# microvboatBOARD.net
KiCad netlist of a schematic drawn in EAGLE
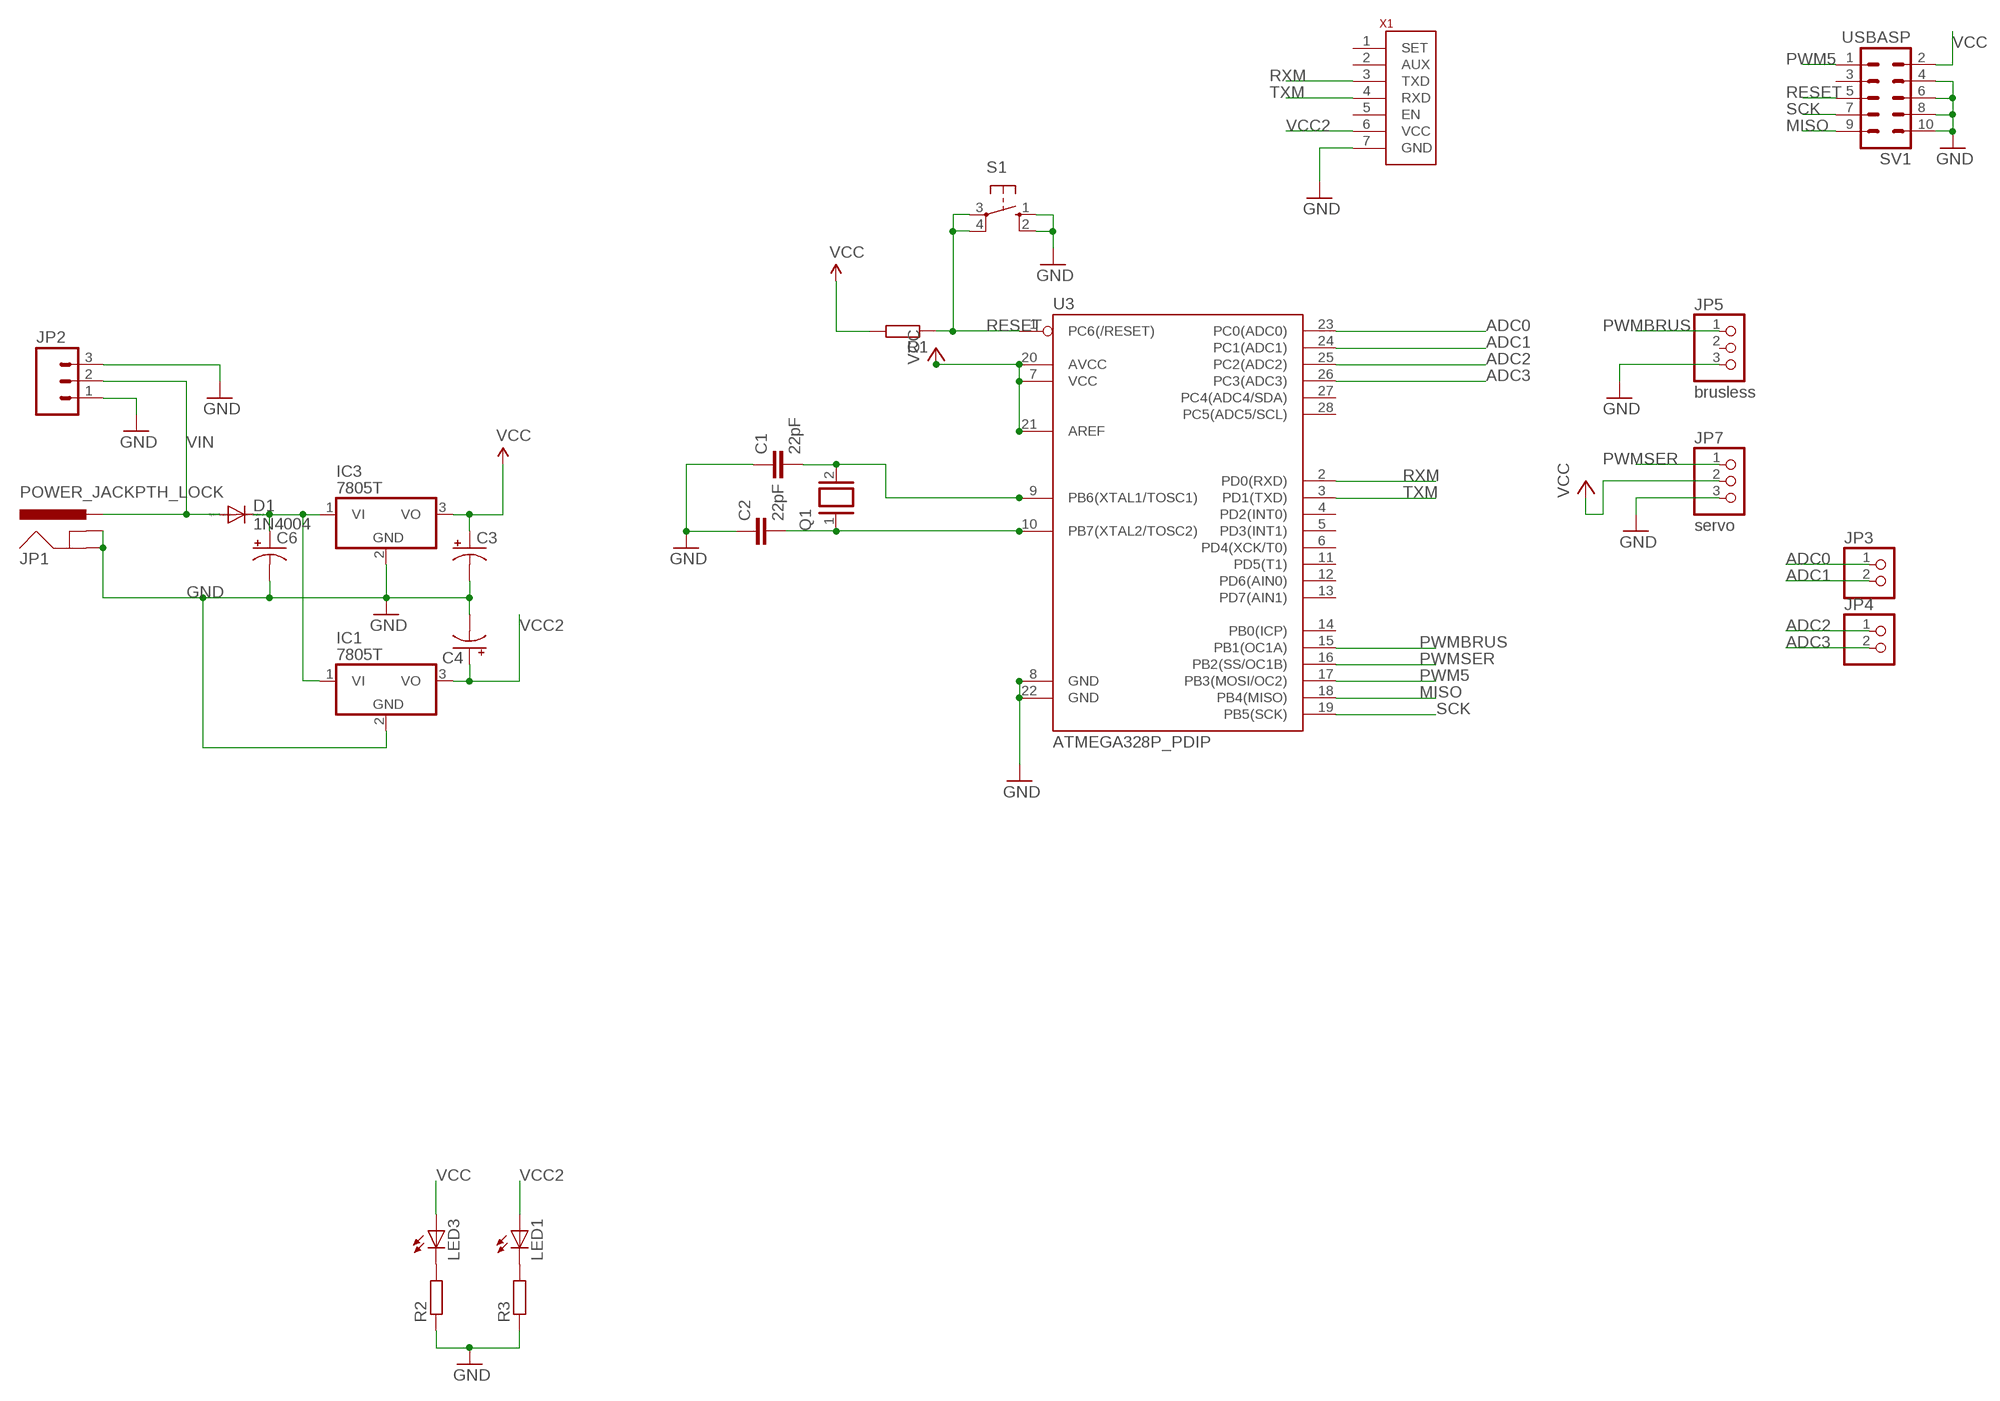
[diagram p0: schematic, sheet 1]

(export (version "E")
  (design (tool "Eeschema 10.0.6"))
  (components
    (comp (ref "C1")
      (value "22pF")
      (footprint "eagle-import:C2.5-3")
      (libsource (lib "eagle-import") (part "C2,5-3"))
    )
    (comp (ref "C2")
      (value "22pF")
      (footprint "eagle-import:C2.5-3")
      (libsource (lib "eagle-import") (part "C2,5-3"))
    )
    (comp (ref "C3")
      (value "CPOL-USE2.5-5")
      (footprint "eagle-import:E2,5-5")
      (libsource (lib "eagle-import") (part "CPOL-USE2.5-5"))
    )
    (comp (ref "C4")
      (value "CPOL-USE2.5-5")
      (footprint "eagle-import:E2,5-5")
      (libsource (lib "eagle-import") (part "CPOL-USE2.5-5"))
    )
    (comp (ref "C6")
      (value "CPOL-USE2.5-5")
      (footprint "eagle-import:E2,5-5")
      (libsource (lib "eagle-import") (part "CPOL-USE2.5-5"))
    )
    (comp (ref "D1")
      (value "1N4004")
      (footprint "eagle-import:DO41-10")
      (libsource (lib "eagle-import") (part "1N4004"))
    )
    (comp (ref "IC1")
      (value "7805T")
      (footprint "eagle-import:TO220H")
      (libsource (lib "eagle-import") (part "78T05"))
    )
    (comp (ref "IC3")
      (value "7805T")
      (footprint "eagle-import:TO220H")
      (libsource (lib "eagle-import") (part "78T05"))
    )
    (comp (ref "JP1")
      (value "POWER_JACKPTH_LOCK")
      (footprint "eagle-import:POWER_JACK_PTH_LOCK")
      (libsource (lib "eagle-import") (part "POWER_JACKPTH_LOCK"))
    )
    (comp (ref "JP2")
      (value "M03POLAR")
      (footprint "eagle-import:MOLEX-1X3")
      (libsource (lib "eagle-import") (part "M03POLAR"))
    )
    (comp (ref "JP3")
      (value "PINHD-1X2")
      (footprint "eagle-import:1X02")
      (libsource (lib "eagle-import") (part "PINHD-1X2"))
    )
    (comp (ref "JP4")
      (value "PINHD-1X2")
      (footprint "eagle-import:1X02")
      (libsource (lib "eagle-import") (part "PINHD-1X2"))
    )
    (comp (ref "JP5")
      (value "brusless")
      (footprint "eagle-import:1X03")
      (libsource (lib "eagle-import") (part "PINHD-1X3"))
    )
    (comp (ref "JP7")
      (value "servo")
      (footprint "eagle-import:1X03")
      (libsource (lib "eagle-import") (part "PINHD-1X3"))
    )
    (comp (ref "LED1")
      (value "LED3MM")
      (footprint "eagle-import:LED3MM")
      (libsource (lib "eagle-import") (part "LED3MM"))
    )
    (comp (ref "LED3")
      (value "LED3MM")
      (footprint "eagle-import:LED3MM")
      (libsource (lib "eagle-import") (part "LED3MM"))
    )
    (comp (ref "Q1")
      (value "XTAL/S")
      (footprint "eagle-import:QS")
      (libsource (lib "eagle-import") (part "XTAL/S"))
    )
    (comp (ref "R1")
      (value "R-EU_0204/7")
      (footprint "eagle-import:0204_7")
      (libsource (lib "eagle-import") (part "R-EU_0204/7"))
    )
    (comp (ref "R2")
      (value "R-EU_0204/7")
      (footprint "eagle-import:0204_7")
      (libsource (lib "eagle-import") (part "R-EU_0204/7"))
    )
    (comp (ref "R3")
      (value "R-EU_0204/7")
      (footprint "eagle-import:0204_7")
      (libsource (lib "eagle-import") (part "R-EU_0204/7"))
    )
    (comp (ref "S1")
      (value "10-XX")
      (footprint "eagle-import:B3F-10XX")
      (fields (field (name "MPN") "B3F-1000"))
      (libsource (lib "eagle-import") (part "10-XX"))
    )
    (comp (ref "SV1")
      (value "USBASP")
      (footprint "eagle-import:ML10")
      (libsource (lib "eagle-import") (part "ML10"))
    )
    (comp (ref "U3")
      (value "ATMEGA328P_PDIP")
      (footprint "eagle-import:DIL28-3")
      (libsource (lib "eagle-import") (part "ATMEGA328P_PDIP"))
    )
    (comp (ref "X1")
      (value "APC220")
      (footprint "eagle-import:APC220")
      (libsource (lib "eagle-import") (part "APC220"))
    )
  )
  (nets
    (net (code "1") (name "/ADC0") (class "Default")
      (node (ref "JP3") (pin "1") (pinfunction "1_1") (pintype "passive"))
      (node (ref "U3") (pin "23") (pinfunction "PC0(ADC0)_23") (pintype "bidirectional"))
    )
    (net (code "2") (name "/ADC1") (class "Default")
      (node (ref "JP3") (pin "2") (pinfunction "2_2") (pintype "passive"))
      (node (ref "U3") (pin "24") (pinfunction "PC1(ADC1)_24") (pintype "bidirectional"))
    )
    (net (code "3") (name "/ADC2") (class "Default")
      (node (ref "JP4") (pin "1") (pinfunction "1_1") (pintype "passive"))
      (node (ref "U3") (pin "25") (pinfunction "PC2(ADC2)_25") (pintype "bidirectional"))
    )
    (net (code "4") (name "/ADC3") (class "Default")
      (node (ref "JP4") (pin "2") (pinfunction "2_2") (pintype "passive"))
      (node (ref "U3") (pin "26") (pinfunction "PC3(ADC3)_26") (pintype "bidirectional"))
    )
    (net (code "5") (name "/MISO") (class "Default")
      (node (ref "SV1") (pin "9") (pinfunction "9_9") (pintype "passive"))
      (node (ref "U3") (pin "18") (pinfunction "PB4(MISO)_18") (pintype "bidirectional"))
    )
    (net (code "6") (name "/PWM5") (class "Default")
      (node (ref "SV1") (pin "1") (pinfunction "1_1") (pintype "passive"))
      (node (ref "U3") (pin "17") (pinfunction "PB3(MOSI/OC2)_17") (pintype "bidirectional"))
    )
    (net (code "7") (name "/PWMBRUS") (class "Default")
      (node (ref "JP5") (pin "1") (pinfunction "1_1") (pintype "passive"))
      (node (ref "U3") (pin "15") (pinfunction "PB1(OC1A)_15") (pintype "bidirectional"))
    )
    (net (code "8") (name "/PWMSER") (class "Default")
      (node (ref "JP7") (pin "1") (pinfunction "1_1") (pintype "passive"))
      (node (ref "U3") (pin "16") (pinfunction "PB2(SS/OC1B)_16") (pintype "bidirectional"))
    )
    (net (code "9") (name "/RESET") (class "Default")
      (node (ref "R1") (pin "1") (pinfunction "1_1") (pintype "passive"))
      (node (ref "S1") (pin "3") (pinfunction "P_3") (pintype "passive"))
      (node (ref "S1") (pin "4") (pinfunction "P1_4") (pintype "passive"))
      (node (ref "SV1") (pin "5") (pinfunction "5_5") (pintype "passive"))
      (node (ref "U3") (pin "1") (pinfunction "PC6(/RESET)_1") (pintype "bidirectional"))
    )
    (net (code "10") (name "/RXM") (class "Default")
      (node (ref "U3") (pin "2") (pinfunction "PD0(RXD)_2") (pintype "bidirectional"))
      (node (ref "X1") (pin "3") (pinfunction "TXD_3") (pintype "bidirectional"))
    )
    (net (code "11") (name "/SCK") (class "Default")
      (node (ref "SV1") (pin "7") (pinfunction "7_7") (pintype "passive"))
      (node (ref "U3") (pin "19") (pinfunction "PB5(SCK)_19") (pintype "bidirectional"))
    )
    (net (code "12") (name "/TXM") (class "Default")
      (node (ref "U3") (pin "3") (pinfunction "PD1(TXD)_3") (pintype "bidirectional"))
      (node (ref "X1") (pin "4") (pinfunction "RXD_4") (pintype "bidirectional"))
    )
    (net (code "13") (name "/VCC2") (class "Default")
      (node (ref "C4") (pin "+") (pinfunction "+_+") (pintype "passive"))
      (node (ref "IC1") (pin "3") (pinfunction "VO_3") (pintype "passive"))
      (node (ref "LED1") (pin "A") (pinfunction "A_A") (pintype "passive"))
      (node (ref "X1") (pin "6") (pinfunction "VCC_6") (pintype "bidirectional"))
    )
    (net (code "14") (name "/VIN") (class "Default")
      (node (ref "D1") (pin "A") (pinfunction "A_A") (pintype "passive"))
      (node (ref "JP1") (pin "PWR") (pinfunction "PWR_PWR") (pintype "bidirectional"))
      (node (ref "JP2") (pin "2") (pinfunction "2_2") (pintype "passive"))
    )
    (net (code "15") (name "GND") (class "Default")
      (node (ref "C1") (pin "1") (pinfunction "1_1") (pintype "passive"))
      (node (ref "C2") (pin "1") (pinfunction "1_1") (pintype "passive"))
      (node (ref "C3") (pin "-") (pinfunction "-_-") (pintype "passive"))
      (node (ref "C4") (pin "-") (pinfunction "-_-") (pintype "passive"))
      (node (ref "C6") (pin "-") (pinfunction "-_-") (pintype "passive"))
      (node (ref "IC1") (pin "2") (pinfunction "GND_2") (pintype "passive"))
      (node (ref "IC3") (pin "2") (pinfunction "GND_2") (pintype "passive"))
      (node (ref "JP1") (pin "GND") (pinfunction "GND_GND") (pintype "bidirectional"))
      (node (ref "JP1") (pin "GNDBREAK") (pinfunction "GNDBREAK_GNDBREAK") (pintype "bidirectional"))
      (node (ref "JP2") (pin "1") (pinfunction "1_1") (pintype "passive"))
      (node (ref "JP2") (pin "3") (pinfunction "3_3") (pintype "passive"))
      (node (ref "JP5") (pin "3") (pinfunction "3_3") (pintype "passive"))
      (node (ref "JP7") (pin "3") (pinfunction "3_3") (pintype "passive"))
      (node (ref "R2") (pin "1") (pinfunction "1_1") (pintype "passive"))
      (node (ref "R3") (pin "1") (pinfunction "1_1") (pintype "passive"))
      (node (ref "S1") (pin "1") (pinfunction "S_1") (pintype "passive"))
      (node (ref "S1") (pin "2") (pinfunction "S1_2") (pintype "passive"))
      (node (ref "SV1") (pin "10") (pinfunction "10_10") (pintype "passive"))
      (node (ref "SV1") (pin "4") (pinfunction "4_4") (pintype "passive"))
      (node (ref "SV1") (pin "6") (pinfunction "6_6") (pintype "passive"))
      (node (ref "SV1") (pin "8") (pinfunction "8_8") (pintype "passive"))
      (node (ref "U3") (pin "22") (pinfunction "GND_22") (pintype "bidirectional"))
      (node (ref "U3") (pin "8") (pinfunction "GND_8") (pintype "bidirectional"))
      (node (ref "X1") (pin "7") (pinfunction "GND_7") (pintype "bidirectional"))
    )
    (net (code "16") (name "Net-(IC1-VI)") (class "Default")
      (node (ref "C6") (pin "+") (pinfunction "+_+") (pintype "passive"))
      (node (ref "D1") (pin "C") (pinfunction "C_C") (pintype "passive"))
      (node (ref "IC1") (pin "1") (pinfunction "VI_1") (pintype "input"))
      (node (ref "IC3") (pin "1") (pinfunction "VI_1") (pintype "input"))
    )
    (net (code "17") (name "Net-(LED1-C)") (class "Default")
      (node (ref "LED1") (pin "K") (pinfunction "C_K") (pintype "passive"))
      (node (ref "R3") (pin "2") (pinfunction "2_2") (pintype "passive"))
    )
    (net (code "18") (name "Net-(LED3-C)") (class "Default")
      (node (ref "LED3") (pin "K") (pinfunction "C_K") (pintype "passive"))
      (node (ref "R2") (pin "2") (pinfunction "2_2") (pintype "passive"))
    )
    (net (code "19") (name "Net-(U3-PB6(XTAL1{slash}TOSC1))") (class "Default")
      (node (ref "C1") (pin "2") (pinfunction "2_2") (pintype "passive"))
      (node (ref "Q1") (pin "2") (pinfunction "2_2") (pintype "passive"))
      (node (ref "U3") (pin "9") (pinfunction "PB6(XTAL1/TOSC1)_9") (pintype "bidirectional"))
    )
    (net (code "20") (name "Net-(U3-PB7(XTAL2{slash}TOSC2))") (class "Default")
      (node (ref "C2") (pin "2") (pinfunction "2_2") (pintype "passive"))
      (node (ref "Q1") (pin "1") (pinfunction "1_1") (pintype "passive"))
      (node (ref "U3") (pin "10") (pinfunction "PB7(XTAL2/TOSC2)_10") (pintype "bidirectional"))
    )
    (net (code "21") (name "VCC") (class "Default")
      (node (ref "C3") (pin "+") (pinfunction "+_+") (pintype "passive"))
      (node (ref "IC3") (pin "3") (pinfunction "VO_3") (pintype "passive"))
      (node (ref "JP7") (pin "2") (pinfunction "2_2") (pintype "passive"))
      (node (ref "LED3") (pin "A") (pinfunction "A_A") (pintype "passive"))
      (node (ref "R1") (pin "2") (pinfunction "2_2") (pintype "passive"))
      (node (ref "SV1") (pin "2") (pinfunction "2_2") (pintype "passive"))
      (node (ref "U3") (pin "20") (pinfunction "AVCC_20") (pintype "bidirectional"))
      (node (ref "U3") (pin "21") (pinfunction "AREF_21") (pintype "bidirectional"))
      (node (ref "U3") (pin "7") (pinfunction "VCC_7") (pintype "bidirectional"))
    )
    (net (code "22") (name "unconnected-(JP5-Pad2)") (class "Default")
      (node (ref "JP5") (pin "2") (pinfunction "2_2") (pintype "passive"))
    )
    (net (code "23") (name "unconnected-(SV1-Pad3)") (class "Default")
      (node (ref "SV1") (pin "3") (pinfunction "3_3") (pintype "passive"))
    )
    (net (code "24") (name "unconnected-(U3-PB0(ICP)-Pad14)") (class "Default")
      (node (ref "U3") (pin "14") (pinfunction "PB0(ICP)_14") (pintype "bidirectional"))
    )
    (net (code "25") (name "unconnected-(U3-PC4(ADC4{slash}SDA)-Pad27)") (class "Default")
      (node (ref "U3") (pin "27") (pinfunction "PC4(ADC4/SDA)_27") (pintype "bidirectional"))
    )
    (net (code "26") (name "unconnected-(U3-PC5(ADC5{slash}SCL)-Pad28)") (class "Default")
      (node (ref "U3") (pin "28") (pinfunction "PC5(ADC5/SCL)_28") (pintype "bidirectional"))
    )
    (net (code "27") (name "unconnected-(U3-PD2(INT0)-Pad4)") (class "Default")
      (node (ref "U3") (pin "4") (pinfunction "PD2(INT0)_4") (pintype "bidirectional"))
    )
    (net (code "28") (name "unconnected-(U3-PD3(INT1)-Pad5)") (class "Default")
      (node (ref "U3") (pin "5") (pinfunction "PD3(INT1)_5") (pintype "bidirectional"))
    )
    (net (code "29") (name "unconnected-(U3-PD4(XCK{slash}T0)-Pad6)") (class "Default")
      (node (ref "U3") (pin "6") (pinfunction "PD4(XCK/T0)_6") (pintype "bidirectional"))
    )
    (net (code "30") (name "unconnected-(U3-PD5(T1)-Pad11)") (class "Default")
      (node (ref "U3") (pin "11") (pinfunction "PD5(T1)_11") (pintype "bidirectional"))
    )
    (net (code "31") (name "unconnected-(U3-PD6(AIN0)-Pad12)") (class "Default")
      (node (ref "U3") (pin "12") (pinfunction "PD6(AIN0)_12") (pintype "bidirectional"))
    )
    (net (code "32") (name "unconnected-(U3-PD7(AIN1)-Pad13)") (class "Default")
      (node (ref "U3") (pin "13") (pinfunction "PD7(AIN1)_13") (pintype "bidirectional"))
    )
    (net (code "33") (name "unconnected-(X1-AUX-Pad2)") (class "Default")
      (node (ref "X1") (pin "2") (pinfunction "AUX_2") (pintype "bidirectional"))
    )
    (net (code "34") (name "unconnected-(X1-EN-Pad5)") (class "Default")
      (node (ref "X1") (pin "5") (pinfunction "EN_5") (pintype "bidirectional"))
    )
    (net (code "35") (name "unconnected-(X1-SET-Pad1)") (class "Default")
      (node (ref "X1") (pin "1") (pinfunction "SET_1") (pintype "bidirectional"))
    )
  )
)
